# PowerInSchematic.net
KiCad netlist of a schematic drawn in Altium Designer
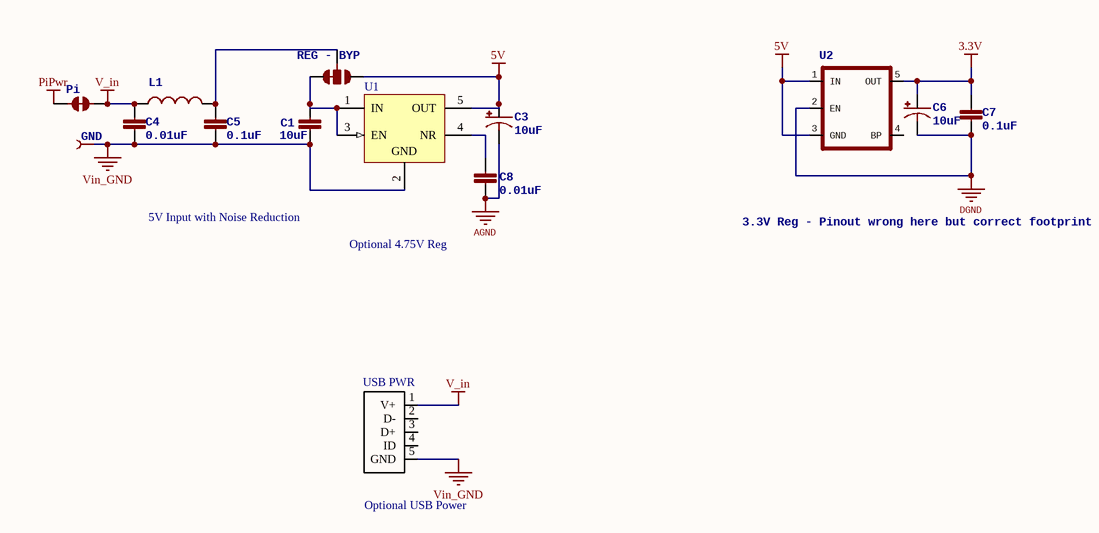
[diagram p0: PowerInSchematic.SchDoc]

(export (version "E")
  (design (tool "Eeschema 10.0.6"))
  (components
    (comp (ref "C1")
      (value "10uF")
      (footprint "0603-CAP")
      (fields (field (name "PART#") "assortment"))
      (libsource (lib "SparkFun-Capacitors") (part "0.1UF-25V-5%(0603)"))
    )
    (comp (ref "C3")
      (value "10uF")
      (footprint "EIA3216")
      (fields
        (field (name "PART#") "Vishay 10μF 16 V dc Tantalum Capacitor MnO2 Solid ±10% tolerance 593D series")
      )
      (libsource (lib "SparkFun-Capacitors") (part "CAP_POL1206"))
    )
    (comp (ref "C4")
      (value "0.01uF")
      (footprint "0603-CAP")
      (fields (field (name "PART#") "assortment"))
      (libsource (lib "SparkFun-Capacitors") (part "0.1UF-25V-5%(0603)"))
    )
    (comp (ref "C5")
      (value "0.1uF")
      (footprint "0603-CAP")
      (fields (field (name "PART#") "assortment"))
      (libsource (lib "SparkFun-Capacitors") (part "0.1UF-25V-5%(0603)"))
    )
    (comp (ref "C6")
      (value "10uF")
      (footprint "EIA3216")
      (fields
        (field (name "PART#") "Vishay 10μF 16 V dc Tantalum Capacitor MnO2 Solid ±10% tolerance 593D series")
      )
      (libsource (lib "SparkFun-Capacitors") (part "CAP_POL1206"))
    )
    (comp (ref "C7")
      (value "0.1uF")
      (footprint "0603-CAP")
      (fields (field (name "PART#") "assortment"))
      (libsource (lib "SparkFun-Capacitors") (part "0.1UF-25V-5%(0603)"))
    )
    (comp (ref "C8")
      (value "0.01uF")
      (footprint "0603-CAP")
      (fields (field (name "PART#") "assortment"))
      (libsource (lib "SparkFun-Capacitors") (part "0.1UF-25V-5%(0603)"))
    )
    (comp (ref "GND")
      (value "TEST-POINT3")
      (footprint "PAD.03X.03")
      (libsource (lib "SparkFun-Passives") (part "TEST-POINT3"))
    )
    (comp (ref "L1")
      (value "~")
      (footprint "0805")
      (fields (field (name "PART#") "mpz2012s331a"))
      (libsource (lib "SparkFun-Passives") (part "INDUCTOR0805"))
    )
    (comp (ref "Pi")
      (value "JUMPER-PAD-2-NC_BY_TRACENO_SILK")
      (footprint "PAD-JUMPER-2-NC_BY_TRACE_NO_SILK")
      (libsource (lib "SparkFun-Passives") (part "JUMPER-PAD-2-NC_BY_TRACENO_SILK"))
    )
    (comp (ref "REG - BYP")
      (value "JUMPER-PAD-3-2OF3_NC_BY_TRACE_SMALL")
      (footprint "3 pad jumper 2 of 3 connected no silk screen")
      (libsource (lib "SparkFun-Passives") (part "JUMPER-PAD-3-2OF3_NC_BY_TRACE_SMALL"))
    )
    (comp (ref "U1")
      (value "Optional 4.75V Reg")
      (footprint "TI-DBV5_N")
      (fields (field (name "MANUFACTURER") "Texas Instruments") (field (name "PARTNUMBER") "TPS793475DBVR"))
      (libsource (lib "TI Power Management Linear Regulator Single Channel LDO (0-350mA)") (part "TPS793475DBVR"))
    )
    (comp (ref "U2")
      (value "3.3V Reg - Pinout wrong here but correct footprint")
      (footprint "TI-DBV5_N")
      (fields (field (name "PART#") "MIC5205-3.3YM5-TR"))
      (libsource (lib "SparkFun-PowerIC") (part "MIC52053.3V"))
    )
    (comp (ref "USB PWR")
      (value "Optional USB Power")
      (footprint "MicroUSB-HRS1")
      (fields (field (name "PART#") "assortment"))
      (libsource (lib "JennicNodeLib") (part "MicroUSB-HRS-ZX62-AB-5PA"))
    )
  )
  (nets
    (net (code "1") (name "3.3V") (class "Default")
      (node (ref "C6") (pin "A") (pinfunction "+_A") (pintype "passive"))
      (node (ref "C7") (pin "1") (pinfunction "1_1") (pintype "passive"))
      (node (ref "U2") (pin "5") (pinfunction "OUT_5") (pintype "passive"))
    )
    (net (code "2") (name "5V") (class "Default")
      (node (ref "C3") (pin "A") (pinfunction "+_A") (pintype "passive"))
      (node (ref "REG - BYP") (pin "1") (pinfunction "1_1") (pintype "passive"))
      (node (ref "U1") (pin "5") (pinfunction "OUT_5") (pintype "power_in"))
      (node (ref "U2") (pin "1") (pinfunction "IN_1") (pintype "passive"))
      (node (ref "U2") (pin "3") (pinfunction "GND_3") (pintype "passive"))
    )
    (net (code "3") (name "AGND") (class "Default")
      (node (ref "C3") (pin "C") (pinfunction "-_C") (pintype "passive"))
      (node (ref "C8") (pin "2") (pinfunction "2_2") (pintype "passive"))
    )
    (net (code "4") (name "DGND") (class "Default")
      (node (ref "C6") (pin "C") (pinfunction "-_C") (pintype "passive"))
      (node (ref "C7") (pin "2") (pinfunction "2_2") (pintype "passive"))
      (node (ref "U2") (pin "2") (pinfunction "EN_2") (pintype "passive"))
    )
    (net (code "5") (name "Net-(C5-Pad1)") (class "Default")
      (node (ref "C5") (pin "1") (pinfunction "1_1") (pintype "passive"))
      (node (ref "L1") (pin "2") (pinfunction "2_2") (pintype "passive"))
      (node (ref "REG - BYP") (pin "2") (pinfunction "2_2") (pintype "passive"))
    )
    (net (code "6") (name "Net-(U1-EN)") (class "Default")
      (node (ref "C1") (pin "1") (pinfunction "1_1") (pintype "passive"))
      (node (ref "REG - BYP") (pin "3") (pinfunction "3_3") (pintype "passive"))
      (node (ref "U1") (pin "1") (pinfunction "IN_1") (pintype "power_in"))
      (node (ref "U1") (pin "3") (pinfunction "EN_3") (pintype "input"))
    )
    (net (code "7") (name "Net-(U1-NR)") (class "Default")
      (node (ref "C8") (pin "1") (pinfunction "1_1") (pintype "passive"))
      (node (ref "U1") (pin "4") (pinfunction "NR_4") (pintype "passive"))
    )
    (net (code "8") (name "PiPwr") (class "Default")
      (node (ref "Pi") (pin "1") (pinfunction "1_1") (pintype "passive"))
    )
    (net (code "9") (name "V_in") (class "Default")
      (node (ref "C4") (pin "1") (pinfunction "1_1") (pintype "passive"))
      (node (ref "L1") (pin "1") (pinfunction "1_1") (pintype "passive"))
      (node (ref "Pi") (pin "2") (pinfunction "2_2") (pintype "passive"))
      (node (ref "USB PWR") (pin "1") (pinfunction "V+_1") (pintype "passive"))
    )
    (net (code "10") (name "Vin_GND") (class "Default")
      (node (ref "C1") (pin "2") (pinfunction "2_2") (pintype "passive"))
      (node (ref "C4") (pin "2") (pinfunction "2_2") (pintype "passive"))
      (node (ref "C5") (pin "2") (pinfunction "2_2") (pintype "passive"))
      (node (ref "GND") (pin "P$1") (pinfunction "1_P$1") (pintype "passive"))
      (node (ref "U1") (pin "2") (pinfunction "GND_2") (pintype "power_in"))
      (node (ref "USB PWR") (pin "5") (pinfunction "GND_5") (pintype "passive"))
    )
    (net (code "11") (name "unconnected-(U2-BP-Pad4)") (class "Default")
      (node (ref "U2") (pin "4") (pinfunction "BP_4") (pintype "passive"))
    )
    (net (code "12") (name "unconnected-(USB PWR-D+-Pad3)") (class "Default")
      (node (ref "USB PWR") (pin "3") (pinfunction "D+_3") (pintype "passive"))
    )
    (net (code "13") (name "unconnected-(USB PWR-D--Pad2)") (class "Default")
      (node (ref "USB PWR") (pin "2") (pinfunction "D-_2") (pintype "passive"))
    )
    (net (code "14") (name "unconnected-(USB PWR-ID-Pad4)") (class "Default")
      (node (ref "USB PWR") (pin "4") (pinfunction "ID_4") (pintype "passive"))
    )
  )
)
